# 12_CONSOLE.net
KiCad netlist of a schematic drawn in Altium Designer
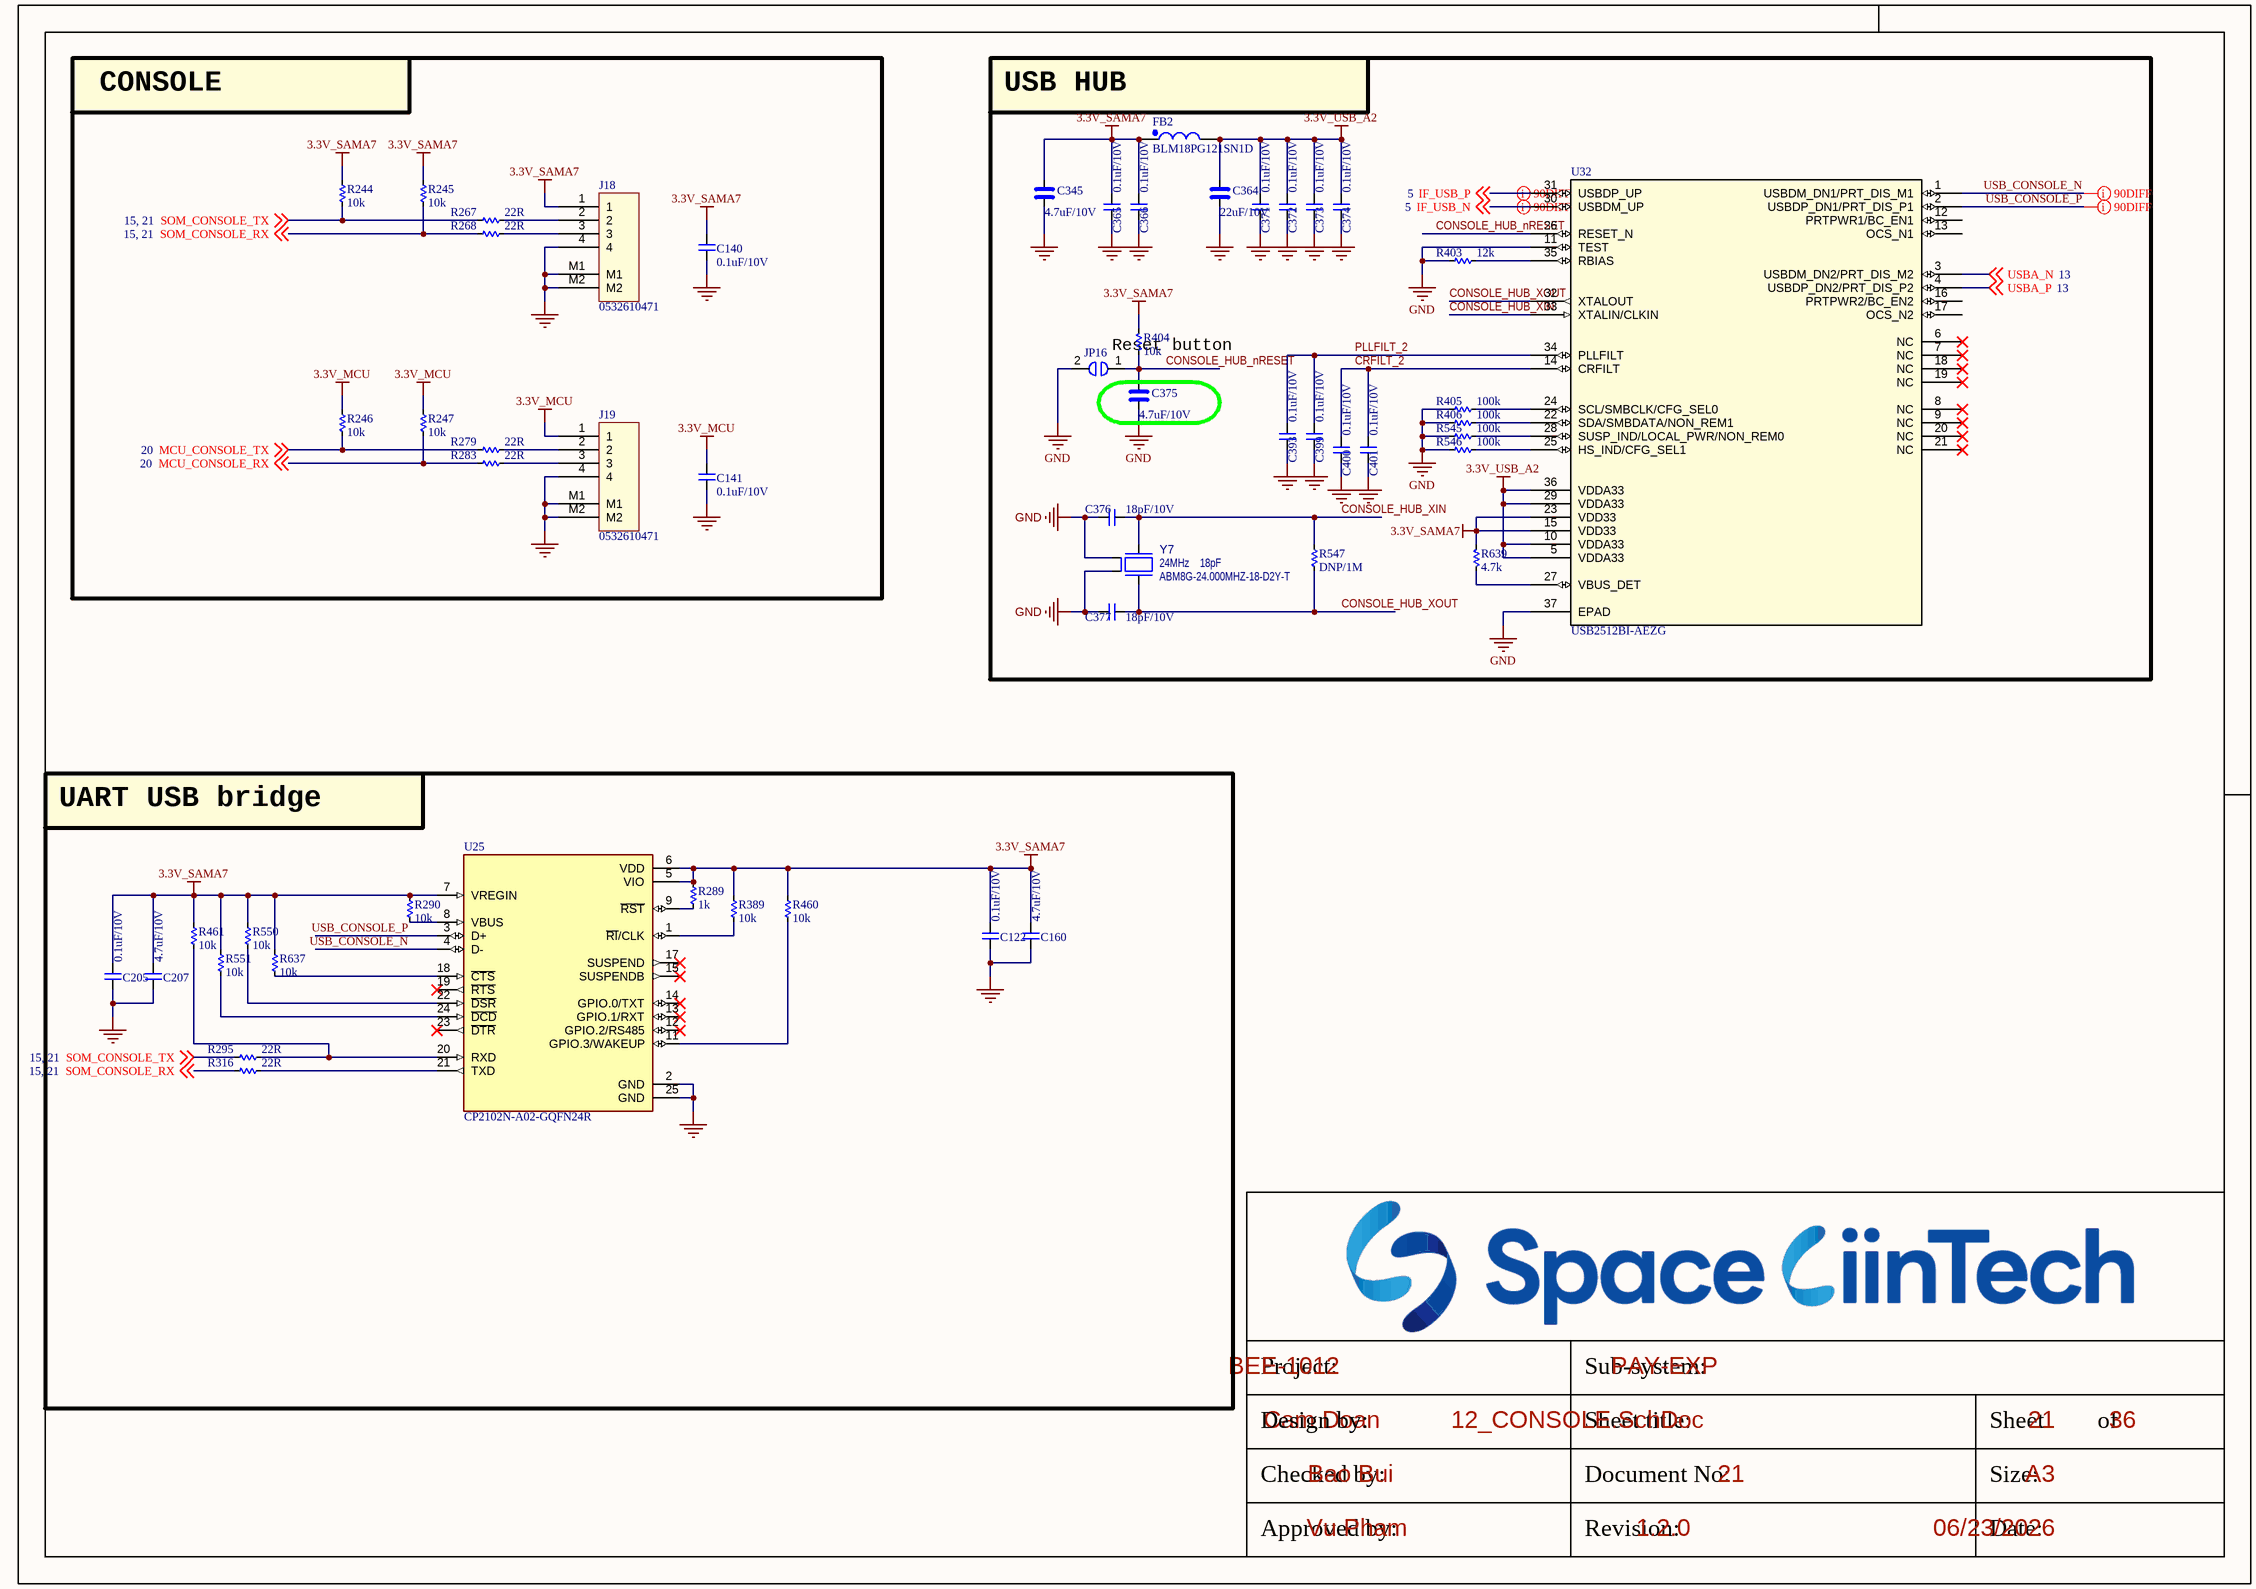
[diagram p0: 12_CONSOLE.SchDoc]

(export (version "E")
  (design (tool "Eeschema 10.0.6"))
  (components
    (comp (ref "C122")
      (value "0.1uF/10V")
      (footprint "CAP_C_1005X60")
      (description "CAP")
      (libsource (lib "LABLIB") (part "_CAP_C_2"))
    )
    (comp (ref "C140")
      (value "0.1uF/10V")
      (footprint "CAP_C_1005X60")
      (description "CAP")
      (libsource (lib "LABLIB") (part "_CAP_C_2"))
    )
    (comp (ref "C141")
      (value "0.1uF/10V")
      (footprint "CAP_C_1005X60")
      (description "CAP")
      (libsource (lib "LABLIB") (part "_CAP_C_2"))
    )
    (comp (ref "C160")
      (value "4.7uF/10V")
      (footprint "CAP_C_1005X60")
      (description "CAP")
      (libsource (lib "LABLIB") (part "_CAP_C_2"))
    )
    (comp (ref "C205")
      (value "0.1uF/10V")
      (footprint "CAP_C_1005X60")
      (description "CAP")
      (libsource (lib "LABLIB") (part "_CAP_C_2"))
    )
    (comp (ref "C207")
      (value "4.7uF/10V")
      (footprint "CAP_C_1005X60")
      (description "CAP")
      (libsource (lib "LABLIB") (part "_CAP_C_2"))
    )
    (comp (ref "C345")
      (value "4.7uF/10V")
      (footprint "CAP_C_1608X80")
      (description "CAP CHIP High Value")
      (libsource (lib "LABLIB") (part "_CAP_C_High_2"))
    )
    (comp (ref "C364")
      (value "22uF/10V")
      (footprint "CAP_C_1608X80")
      (description "CAP CHIP High Value")
      (libsource (lib "LABLIB") (part "_CAP_C_High_2"))
    )
    (comp (ref "C365")
      (value "0.1uF/10V")
      (footprint "CAP_C_1005X60")
      (description "CAP CHIP")
      (libsource (lib "LABLIB") (part "_CAP_C_2"))
    )
    (comp (ref "C366")
      (value "0.1uF/10V")
      (footprint "CAP_C_1005X60")
      (description "CAP CHIP")
      (libsource (lib "LABLIB") (part "_CAP_C_2"))
    )
    (comp (ref "C371")
      (value "0.1uF/10V")
      (footprint "CAP_C_1005X60")
      (description "CAP CHIP")
      (libsource (lib "LABLIB") (part "_CAP_C_2"))
    )
    (comp (ref "C372")
      (value "0.1uF/10V")
      (footprint "CAP_C_1005X60")
      (description "CAP CHIP")
      (libsource (lib "LABLIB") (part "_CAP_C_2"))
    )
    (comp (ref "C373")
      (value "0.1uF/10V")
      (footprint "CAP_C_1005X60")
      (description "CAP CHIP")
      (libsource (lib "LABLIB") (part "_CAP_C_2"))
    )
    (comp (ref "C374")
      (value "0.1uF/10V")
      (footprint "CAP_C_1005X60")
      (description "CAP CHIP")
      (libsource (lib "LABLIB") (part "_CAP_C_2"))
    )
    (comp (ref "C375")
      (value "4.7uF/10V")
      (footprint "CAP_C_1608X80")
      (description "CAP CHIP High Value")
      (libsource (lib "LABLIB") (part "_CAP_C_High_2"))
    )
    (comp (ref "C376")
      (value "18pF/10V")
      (footprint "CAP_C_1005X60")
      (description "CAP CHIP")
      (libsource (lib "LABLIB") (part "_CAP_C_2"))
    )
    (comp (ref "C377")
      (value "18pF/10V")
      (footprint "CAP_C_1005X60")
      (description "CAP CHIP")
      (libsource (lib "LABLIB") (part "_CAP_C_2"))
    )
    (comp (ref "C393")
      (value "0.1uF/10V")
      (footprint "CAP_C_1005X60")
      (description "CAP CHIP")
      (libsource (lib "LABLIB") (part "_CAP_C_2"))
    )
    (comp (ref "C399")
      (value "0.1uF/10V")
      (footprint "CAP_C_1005X60")
      (description "CAP CHIP")
      (libsource (lib "LABLIB") (part "_CAP_C_2"))
    )
    (comp (ref "C400")
      (value "0.1uF/10V")
      (footprint "CAP_C_1005X60")
      (description "CAP CHIP")
      (libsource (lib "LABLIB") (part "_CAP_C_2"))
    )
    (comp (ref "C401")
      (value "0.1uF/10V")
      (footprint "CAP_C_1005X60")
      (description "CAP CHIP")
      (libsource (lib "LABLIB") (part "_CAP_C_2"))
    )
    (comp (ref "FB2")
      (value "BLM18PG121SN1D")
      (footprint "IND_C_1608X60")
      (libsource (lib "LABLIB") (part "_IND"))
    )
    (comp (ref "J18")
      (value "0532610471")
      (footprint "MOLEX_0532610471")
      (libsource (lib "LABLIB") (part "Header 4x1_2M"))
    )
    (comp (ref "J19")
      (value "0532610471")
      (footprint "MOLEX_0532610471")
      (libsource (lib "LABLIB") (part "Header 4x1_2M"))
    )
    (comp (ref "JP16")
      (value "~")
      (footprint "TESTPOINT_SHORT_120X100_60")
      (libsource (lib "LABLIB") (part "JUMPER_1_1"))
    )
    (comp (ref "R244")
      (value "10k")
      (footprint "RES_C_1005X40")
      (description "RES")
      (libsource (lib "LABLIB") (part "_RES_B_2"))
    )
    (comp (ref "R245")
      (value "10k")
      (footprint "RES_C_1005X40")
      (description "RES")
      (libsource (lib "LABLIB") (part "_RES_B_2"))
    )
    (comp (ref "R246")
      (value "10k")
      (footprint "RES_C_1005X40")
      (description "RES")
      (libsource (lib "LABLIB") (part "_RES_B_2"))
    )
    (comp (ref "R247")
      (value "10k")
      (footprint "RES_C_1005X40")
      (description "RES")
      (libsource (lib "LABLIB") (part "_RES_B_2"))
    )
    (comp (ref "R267")
      (value "22R")
      (footprint "RES_C_1005X40")
      (description "RES")
      (libsource (lib "LABLIB") (part "_RES_B_2"))
    )
    (comp (ref "R268")
      (value "22R")
      (footprint "RES_C_1005X40")
      (description "RES")
      (libsource (lib "LABLIB") (part "_RES_B_2"))
    )
    (comp (ref "R279")
      (value "22R")
      (footprint "RES_C_1005X40")
      (description "RES")
      (libsource (lib "LABLIB") (part "_RES_B_2"))
    )
    (comp (ref "R283")
      (value "22R")
      (footprint "RES_C_1005X40")
      (description "RES")
      (libsource (lib "LABLIB") (part "_RES_B_2"))
    )
    (comp (ref "R289")
      (value "1k")
      (footprint "RES_C_1005X40")
      (description "RES")
      (libsource (lib "LABLIB") (part "_RES_B_2"))
    )
    (comp (ref "R290")
      (value "10k")
      (footprint "RES_C_1005X40")
      (description "RES")
      (libsource (lib "LABLIB") (part "_RES_B_2"))
    )
    (comp (ref "R295")
      (value "22R")
      (footprint "RES_C_1005X40")
      (description "RES")
      (libsource (lib "LABLIB") (part "_RES_B_2"))
    )
    (comp (ref "R316")
      (value "22R")
      (footprint "RES_C_1005X40")
      (description "RES")
      (libsource (lib "LABLIB") (part "_RES_B_2"))
    )
    (comp (ref "R389")
      (value "10k")
      (footprint "RES_C_1005X40")
      (description "RES")
      (libsource (lib "LABLIB") (part "_RES_B_2"))
    )
    (comp (ref "R403")
      (value "12k")
      (footprint "RES_C_1005X40")
      (description "RES")
      (libsource (lib "LABLIB") (part "_RES_B_2"))
    )
    (comp (ref "R404")
      (value "10k")
      (footprint "RES_C_1005X40")
      (description "RES")
      (libsource (lib "LABLIB") (part "_RES_B_2"))
    )
    (comp (ref "R405")
      (value "100k")
      (footprint "RES_C_1005X40")
      (description "RES")
      (libsource (lib "LABLIB") (part "_RES_B_2"))
    )
    (comp (ref "R406")
      (value "100k")
      (footprint "RES_C_1005X40")
      (description "RES")
      (libsource (lib "LABLIB") (part "_RES_B_2"))
    )
    (comp (ref "R460")
      (value "10k")
      (footprint "RES_C_1005X40")
      (description "RES")
      (libsource (lib "LABLIB") (part "_RES_B_2"))
    )
    (comp (ref "R461")
      (value "10k")
      (footprint "RES_C_1005X40")
      (description "RES")
      (libsource (lib "LABLIB") (part "_RES_B_2"))
    )
    (comp (ref "R545")
      (value "100k")
      (footprint "RES_C_1005X40")
      (description "RES")
      (libsource (lib "LABLIB") (part "_RES_B_2"))
    )
    (comp (ref "R546")
      (value "100k")
      (footprint "RES_C_1005X40")
      (description "RES")
      (libsource (lib "LABLIB") (part "_RES_B_2"))
    )
    (comp (ref "R547")
      (value "DNP/1M")
      (footprint "RES_C_1005X40")
      (description "RES")
      (libsource (lib "LABLIB") (part "_RES_B_2"))
    )
    (comp (ref "R550")
      (value "10k")
      (footprint "RES_C_1005X40")
      (description "RES")
      (libsource (lib "LABLIB") (part "_RES_B_2"))
    )
    (comp (ref "R551")
      (value "10k")
      (footprint "RES_C_1005X40")
      (description "RES")
      (libsource (lib "LABLIB") (part "_RES_B_2"))
    )
    (comp (ref "R637")
      (value "10k")
      (footprint "RES_C_1005X40")
      (description "RES")
      (libsource (lib "LABLIB") (part "_RES_B_2"))
    )
    (comp (ref "R639")
      (value "4.7k")
      (footprint "RES_C_1005X40")
      (description "RES")
      (libsource (lib "LABLIB") (part "_RES_B_2"))
    )
    (comp (ref "U25")
      (value "CP2102N-A02-GQFN24R")
      (footprint "QFN50P400X400X80-25N")
      (libsource (lib "LABLIB") (part "IC_USB_toUART_CP2102N-A02-GQFN24R"))
    )
    (comp (ref "U32")
      (value "USB2512BI-AEZG")
      (footprint "QFN36_6X6MC_MCH")
      (description "Description")
      (fields (field (name "COPYRIGHT") "Copyright (C) 2026 Ultra Librarian. All rights reserved."))
      (libsource (lib "LABLIB") (part "IC_USB_HUB_USB2512BI-AEZG"))
    )
    (comp (ref "Y7")
      (value "24MHz")
      (footprint "CRYSTAL_ABM8G")
      (description "Crystal")
      (fields
        (field (name "LOAD CAPACITANCE") "18pF")
        (field (name "MANUFACTURER PART NUMBER 1") "ABM8G-24.000MHZ-18-D2Y-T")
        (field (name "Comment") "Crystal 4 Pins")
        (field (name "OWNER") "Mark Loper")
      )
      (libsource (lib "MCHP-CDB") (part "Crystal 4 Pins"))
    )
  )
  (nets
    (net (code "1") (name "/CONSOLE_HUB_XIN") (class "Default")
      (node (ref "C376") (pin "1") (pinfunction "1_1") (pintype "passive"))
      (node (ref "R547") (pin "1") (pinfunction "1_1") (pintype "passive"))
      (node (ref "U32") (pin "33") (pinfunction "XTALIN/CLKIN_33") (pintype "input"))
      (node (ref "Y7") (pin "3") (pinfunction "Osc2_3") (pintype "passive"))
    )
    (net (code "2") (name "/CONSOLE_HUB_XOUT") (class "Default")
      (node (ref "C377") (pin "1") (pinfunction "1_1") (pintype "passive"))
      (node (ref "R547") (pin "2") (pinfunction "2_2") (pintype "passive"))
      (node (ref "U32") (pin "32") (pinfunction "XTALOUT_32") (pintype "output"))
      (node (ref "Y7") (pin "1") (pinfunction "Osc1_1") (pintype "passive"))
    )
    (net (code "3") (name "/CONSOLE_HUB_nRESET") (class "Default")
      (node (ref "C375") (pin "1") (pinfunction "1_1") (pintype "passive"))
      (node (ref "JP16") (pin "1") (pinfunction "1_1") (pintype "passive"))
      (node (ref "R404") (pin "2") (pinfunction "2_2") (pintype "passive"))
      (node (ref "U32") (pin "26") (pinfunction "RESET_N_26") (pintype "bidirectional"))
    )
    (net (code "4") (name "/CRFILT_2") (class "Default")
      (node (ref "C400") (pin "2") (pinfunction "2_2") (pintype "passive"))
      (node (ref "C401") (pin "2") (pinfunction "2_2") (pintype "passive"))
      (node (ref "U32") (pin "14") (pinfunction "CRFILT_14") (pintype "bidirectional"))
    )
    (net (code "5") (name "/PLLFILT_2") (class "Default")
      (node (ref "C393") (pin "2") (pinfunction "2_2") (pintype "passive"))
      (node (ref "C399") (pin "2") (pinfunction "2_2") (pintype "passive"))
      (node (ref "U32") (pin "34") (pinfunction "PLLFILT_34") (pintype "bidirectional"))
    )
    (net (code "6") (name "/USB_CONSOLE_N") (class "Default")
      (node (ref "U25") (pin "4") (pinfunction "D-_4") (pintype "bidirectional"))
      (node (ref "U32") (pin "1") (pinfunction "USBDM_DN1/PRT_DIS_M1_1") (pintype "bidirectional"))
    )
    (net (code "7") (name "/USB_CONSOLE_P") (class "Default")
      (node (ref "U25") (pin "3") (pinfunction "D+_3") (pintype "bidirectional"))
      (node (ref "U32") (pin "2") (pinfunction "USBDP_DN1/PRT_DIS_P1_2") (pintype "bidirectional"))
    )
    (net (code "8") (name "3.3V_MCU") (class "Default")
      (node (ref "C141") (pin "2") (pinfunction "2_2") (pintype "passive"))
      (node (ref "J19") (pin "1") (pinfunction "1_1") (pintype "passive"))
      (node (ref "R246") (pin "2") (pinfunction "2_2") (pintype "passive"))
      (node (ref "R247") (pin "2") (pinfunction "2_2") (pintype "passive"))
    )
    (net (code "9") (name "3.3V_SAMA7") (class "Default")
      (node (ref "C122") (pin "1") (pinfunction "1_1") (pintype "passive"))
      (node (ref "C140") (pin "2") (pinfunction "2_2") (pintype "passive"))
      (node (ref "C160") (pin "1") (pinfunction "1_1") (pintype "passive"))
      (node (ref "C205") (pin "1") (pinfunction "1_1") (pintype "passive"))
      (node (ref "C207") (pin "1") (pinfunction "1_1") (pintype "passive"))
      (node (ref "C345") (pin "1") (pinfunction "1_1") (pintype "passive"))
      (node (ref "C365") (pin "2") (pinfunction "2_2") (pintype "passive"))
      (node (ref "C366") (pin "2") (pinfunction "2_2") (pintype "passive"))
      (node (ref "FB2") (pin "1") (pinfunction "1_1") (pintype "passive"))
      (node (ref "J18") (pin "1") (pinfunction "1_1") (pintype "passive"))
      (node (ref "R244") (pin "2") (pinfunction "2_2") (pintype "passive"))
      (node (ref "R245") (pin "2") (pinfunction "2_2") (pintype "passive"))
      (node (ref "R289") (pin "2") (pinfunction "2_2") (pintype "passive"))
      (node (ref "R290") (pin "2") (pinfunction "2_2") (pintype "passive"))
      (node (ref "R389") (pin "2") (pinfunction "2_2") (pintype "passive"))
      (node (ref "R404") (pin "1") (pinfunction "1_1") (pintype "passive"))
      (node (ref "R460") (pin "2") (pinfunction "2_2") (pintype "passive"))
      (node (ref "R461") (pin "2") (pinfunction "2_2") (pintype "passive"))
      (node (ref "R550") (pin "2") (pinfunction "2_2") (pintype "passive"))
      (node (ref "R551") (pin "2") (pinfunction "2_2") (pintype "passive"))
      (node (ref "R637") (pin "2") (pinfunction "2_2") (pintype "passive"))
      (node (ref "R639") (pin "1") (pinfunction "1_1") (pintype "passive"))
      (node (ref "U25") (pin "5") (pinfunction "VIO_5") (pintype "power_in"))
      (node (ref "U25") (pin "6") (pinfunction "VDD_6") (pintype "power_in"))
      (node (ref "U25") (pin "7") (pinfunction "VREGIN_7") (pintype "input"))
      (node (ref "U32") (pin "15") (pinfunction "VDD33_15") (pintype "power_in"))
      (node (ref "U32") (pin "23") (pinfunction "VDD33_23") (pintype "power_in"))
    )
    (net (code "10") (name "3.3V_USB_A2") (class "Default")
      (node (ref "C364") (pin "1") (pinfunction "1_1") (pintype "passive"))
      (node (ref "C371") (pin "2") (pinfunction "2_2") (pintype "passive"))
      (node (ref "C372") (pin "2") (pinfunction "2_2") (pintype "passive"))
      (node (ref "C373") (pin "2") (pinfunction "2_2") (pintype "passive"))
      (node (ref "C374") (pin "2") (pinfunction "2_2") (pintype "passive"))
      (node (ref "FB2") (pin "2") (pinfunction "2_2") (pintype "passive"))
      (node (ref "U32") (pin "10") (pinfunction "VDDA33_10") (pintype "power_in"))
      (node (ref "U32") (pin "29") (pinfunction "VDDA33_29") (pintype "power_in"))
      (node (ref "U32") (pin "36") (pinfunction "VDDA33_36") (pintype "power_in"))
      (node (ref "U32") (pin "5") (pinfunction "VDDA33_5") (pintype "power_in"))
    )
    (net (code "11") (name "GND") (class "Default")
      (node (ref "C122") (pin "2") (pinfunction "2_2") (pintype "passive"))
      (node (ref "C140") (pin "1") (pinfunction "1_1") (pintype "passive"))
      (node (ref "C141") (pin "1") (pinfunction "1_1") (pintype "passive"))
      (node (ref "C160") (pin "2") (pinfunction "2_2") (pintype "passive"))
      (node (ref "C205") (pin "2") (pinfunction "2_2") (pintype "passive"))
      (node (ref "C207") (pin "2") (pinfunction "2_2") (pintype "passive"))
      (node (ref "C345") (pin "2") (pinfunction "2_2") (pintype "passive"))
      (node (ref "C364") (pin "2") (pinfunction "2_2") (pintype "passive"))
      (node (ref "C365") (pin "1") (pinfunction "1_1") (pintype "passive"))
      (node (ref "C366") (pin "1") (pinfunction "1_1") (pintype "passive"))
      (node (ref "C371") (pin "1") (pinfunction "1_1") (pintype "passive"))
      (node (ref "C372") (pin "1") (pinfunction "1_1") (pintype "passive"))
      (node (ref "C373") (pin "1") (pinfunction "1_1") (pintype "passive"))
      (node (ref "C374") (pin "1") (pinfunction "1_1") (pintype "passive"))
      (node (ref "C375") (pin "2") (pinfunction "2_2") (pintype "passive"))
      (node (ref "C376") (pin "2") (pinfunction "2_2") (pintype "passive"))
      (node (ref "C377") (pin "2") (pinfunction "2_2") (pintype "passive"))
      (node (ref "C393") (pin "1") (pinfunction "1_1") (pintype "passive"))
      (node (ref "C399") (pin "1") (pinfunction "1_1") (pintype "passive"))
      (node (ref "C400") (pin "1") (pinfunction "1_1") (pintype "passive"))
      (node (ref "C401") (pin "1") (pinfunction "1_1") (pintype "passive"))
      (node (ref "J18") (pin "4") (pinfunction "4_4") (pintype "passive"))
      (node (ref "J18") (pin "M1") (pinfunction "M1_M1") (pintype "passive"))
      (node (ref "J18") (pin "M2") (pinfunction "M2_M2") (pintype "passive"))
      (node (ref "J19") (pin "4") (pinfunction "4_4") (pintype "passive"))
      (node (ref "J19") (pin "M1") (pinfunction "M1_M1") (pintype "passive"))
      (node (ref "J19") (pin "M2") (pinfunction "M2_M2") (pintype "passive"))
      (node (ref "JP16") (pin "2") (pinfunction "2_2") (pintype "passive"))
      (node (ref "R403") (pin "1") (pinfunction "1_1") (pintype "passive"))
      (node (ref "R405") (pin "1") (pinfunction "1_1") (pintype "passive"))
      (node (ref "R406") (pin "1") (pinfunction "1_1") (pintype "passive"))
      (node (ref "R545") (pin "1") (pinfunction "1_1") (pintype "passive"))
      (node (ref "R546") (pin "1") (pinfunction "1_1") (pintype "passive"))
      (node (ref "U25") (pin "2") (pinfunction "GND_2") (pintype "power_in"))
      (node (ref "U25") (pin "25") (pinfunction "GND_25") (pintype "power_in"))
      (node (ref "U32") (pin "11") (pinfunction "TEST_11") (pintype "bidirectional"))
      (node (ref "U32") (pin "37") (pinfunction "EPAD_37") (pintype "passive"))
      (node (ref "Y7") (pin "2") (pinfunction "GND_2") (pintype "power_in"))
      (node (ref "Y7") (pin "4") (pinfunction "GND_4") (pintype "power_in"))
    )
    (net (code "12") (name "IF_USB_N") (class "Default")
      (node (ref "U32") (pin "30") (pinfunction "USBDM_UP_30") (pintype "bidirectional"))
    )
    (net (code "13") (name "IF_USB_P") (class "Default")
      (node (ref "U32") (pin "31") (pinfunction "USBDP_UP_31") (pintype "bidirectional"))
    )
    (net (code "14") (name "MCU_CONSOLE_RX") (class "Default")
      (node (ref "R247") (pin "1") (pinfunction "1_1") (pintype "passive"))
      (node (ref "R283") (pin "2") (pinfunction "2_2") (pintype "passive"))
    )
    (net (code "15") (name "MCU_CONSOLE_TX") (class "Default")
      (node (ref "R246") (pin "1") (pinfunction "1_1") (pintype "passive"))
      (node (ref "R279") (pin "2") (pinfunction "2_2") (pintype "passive"))
    )
    (net (code "16") (name "Net-(J18-Pad2)") (class "Default")
      (node (ref "J18") (pin "2") (pinfunction "2_2") (pintype "passive"))
      (node (ref "R267") (pin "1") (pinfunction "1_1") (pintype "passive"))
    )
    (net (code "17") (name "Net-(J18-Pad3)") (class "Default")
      (node (ref "J18") (pin "3") (pinfunction "3_3") (pintype "passive"))
      (node (ref "R268") (pin "1") (pinfunction "1_1") (pintype "passive"))
    )
    (net (code "18") (name "Net-(J19-Pad2)") (class "Default")
      (node (ref "J19") (pin "2") (pinfunction "2_2") (pintype "passive"))
      (node (ref "R279") (pin "1") (pinfunction "1_1") (pintype "passive"))
    )
    (net (code "19") (name "Net-(J19-Pad3)") (class "Default")
      (node (ref "J19") (pin "3") (pinfunction "3_3") (pintype "passive"))
      (node (ref "R283") (pin "1") (pinfunction "1_1") (pintype "passive"))
    )
    (net (code "20") (name "Net-(U25-GPIO.3{slash}WAKEUP)") (class "Default")
      (node (ref "R460") (pin "1") (pinfunction "1_1") (pintype "passive"))
      (node (ref "U25") (pin "11") (pinfunction "GPIO.3/WAKEUP_11") (pintype "bidirectional"))
    )
    (net (code "21") (name "Net-(U25-RXD)") (class "Default")
      (node (ref "R295") (pin "1") (pinfunction "1_1") (pintype "passive"))
      (node (ref "R461") (pin "1") (pinfunction "1_1") (pintype "passive"))
      (node (ref "U25") (pin "20") (pinfunction "RXD_20") (pintype "input"))
    )
    (net (code "22") (name "Net-(U25-TXD)") (class "Default")
      (node (ref "R316") (pin "1") (pinfunction "1_1") (pintype "passive"))
      (node (ref "U25") (pin "21") (pinfunction "TXD_21") (pintype "output"))
    )
    (net (code "23") (name "Net-(U25-VBUS)") (class "Default")
      (node (ref "R290") (pin "1") (pinfunction "1_1") (pintype "passive"))
      (node (ref "U25") (pin "8") (pinfunction "VBUS_8") (pintype "input"))
    )
    (net (code "24") (name "Net-(U25-~{CTS})") (class "Default")
      (node (ref "R637") (pin "1") (pinfunction "1_1") (pintype "passive"))
      (node (ref "U25") (pin "18") (pinfunction "~{CTS}_18") (pintype "input"))
    )
    (net (code "25") (name "Net-(U25-~{DCD})") (class "Default")
      (node (ref "R551") (pin "1") (pinfunction "1_1") (pintype "passive"))
      (node (ref "U25") (pin "24") (pinfunction "~{DCD}_24") (pintype "input"))
    )
    (net (code "26") (name "Net-(U25-~{DSR})") (class "Default")
      (node (ref "R550") (pin "1") (pinfunction "1_1") (pintype "passive"))
      (node (ref "U25") (pin "22") (pinfunction "~{DSR}_22") (pintype "input"))
    )
    (net (code "27") (name "Net-(U25-~{RI}{slash}CLK)") (class "Default")
      (node (ref "R389") (pin "1") (pinfunction "1_1") (pintype "passive"))
      (node (ref "U25") (pin "1") (pinfunction "~{RI}/CLK_1") (pintype "bidirectional"))
    )
    (net (code "28") (name "Net-(U25-~{RST})") (class "Default")
      (node (ref "R289") (pin "1") (pinfunction "1_1") (pintype "passive"))
      (node (ref "U25") (pin "9") (pinfunction "~{RST}_9") (pintype "bidirectional"))
    )
    (net (code "29") (name "Net-(U32-HS_IND{slash}CFG_SEL1)") (class "Default")
      (node (ref "R546") (pin "2") (pinfunction "2_2") (pintype "passive"))
      (node (ref "U32") (pin "25") (pinfunction "HS_IND/CFG_SEL1_25") (pintype "bidirectional"))
    )
    (net (code "30") (name "Net-(U32-RBIAS)") (class "Default")
      (node (ref "R403") (pin "2") (pinfunction "2_2") (pintype "passive"))
      (node (ref "U32") (pin "35") (pinfunction "RBIAS_35") (pintype "bidirectional"))
    )
    (net (code "31") (name "Net-(U32-SCL{slash}SMBCLK{slash}CFG_SEL0)") (class "Default")
      (node (ref "R405") (pin "2") (pinfunction "2_2") (pintype "passive"))
      (node (ref "U32") (pin "24") (pinfunction "SCL/SMBCLK/CFG_SEL0_24") (pintype "bidirectional"))
    )
    (net (code "32") (name "Net-(U32-SDA{slash}SMBDATA{slash}NON_REM1)") (class "Default")
      (node (ref "R406") (pin "2") (pinfunction "2_2") (pintype "passive"))
      (node (ref "U32") (pin "22") (pinfunction "SDA/SMBDATA/NON_REM1_22") (pintype "bidirectional"))
    )
    (net (code "33") (name "Net-(U32-SUSP_IND{slash}LOCAL_PWR{slash}NON_REM0)") (class "Default")
      (node (ref "R545") (pin "2") (pinfunction "2_2") (pintype "passive"))
      (node (ref "U32") (pin "28") (pinfunction "SUSP_IND/LOCAL_PWR/NON_REM0_28") (pintype "bidirectional"))
    )
    (net (code "34") (name "Net-(U32-VBUS_DET)") (class "Default")
      (node (ref "R639") (pin "2") (pinfunction "2_2") (pintype "passive"))
      (node (ref "U32") (pin "27") (pinfunction "VBUS_DET_27") (pintype "bidirectional"))
    )
    (net (code "35") (name "SOM_CONSOLE_RX") (class "Default")
      (node (ref "R245") (pin "1") (pinfunction "1_1") (pintype "passive"))
      (node (ref "R268") (pin "2") (pinfunction "2_2") (pintype "passive"))
      (node (ref "R316") (pin "2") (pinfunction "2_2") (pintype "passive"))
    )
    (net (code "36") (name "SOM_CONSOLE_TX") (class "Default")
      (node (ref "R244") (pin "1") (pinfunction "1_1") (pintype "passive"))
      (node (ref "R267") (pin "2") (pinfunction "2_2") (pintype "passive"))
      (node (ref "R295") (pin "2") (pinfunction "2_2") (pintype "passive"))
    )
    (net (code "37") (name "USBA_N") (class "Default")
      (node (ref "U32") (pin "3") (pinfunction "USBDM_DN2/PRT_DIS_M2_3") (pintype "bidirectional"))
    )
    (net (code "38") (name "USBA_P") (class "Default")
      (node (ref "U32") (pin "4") (pinfunction "USBDP_DN2/PRT_DIS_P2_4") (pintype "bidirectional"))
    )
    (net (code "39") (name "unconnected-(U25-GPIO.0{slash}TXT-Pad14)") (class "Default")
      (node (ref "U25") (pin "14") (pinfunction "GPIO.0/TXT_14") (pintype "bidirectional+no_connect"))
    )
    (net (code "40") (name "unconnected-(U25-GPIO.1{slash}RXT-Pad13)") (class "Default")
      (node (ref "U25") (pin "13") (pinfunction "GPIO.1/RXT_13") (pintype "bidirectional+no_connect"))
    )
    (net (code "41") (name "unconnected-(U25-GPIO.2{slash}RS485-Pad12)") (class "Default")
      (node (ref "U25") (pin "12") (pinfunction "GPIO.2/RS485_12") (pintype "bidirectional+no_connect"))
    )
    (net (code "42") (name "unconnected-(U25-SUSPEND-Pad17)") (class "Default")
      (node (ref "U25") (pin "17") (pinfunction "SUSPEND_17") (pintype "output+no_connect"))
    )
    (net (code "43") (name "unconnected-(U25-SUSPENDB-Pad15)") (class "Default")
      (node (ref "U25") (pin "15") (pinfunction "SUSPENDB_15") (pintype "output+no_connect"))
    )
    (net (code "44") (name "unconnected-(U25-~{DTR}-Pad23)") (class "Default")
      (node (ref "U25") (pin "23") (pinfunction "~{DTR}_23") (pintype "output+no_connect"))
    )
    (net (code "45") (name "unconnected-(U25-~{RTS}-Pad19)") (class "Default")
      (node (ref "U25") (pin "19") (pinfunction "~{RTS}_19") (pintype "output+no_connect"))
    )
    (net (code "46") (name "unconnected-(U32-NC-Pad6)") (class "Default")
      (node (ref "U32") (pin "6") (pinfunction "NC_6") (pintype "passive+no_connect"))
    )
    (net (code "47") (name "unconnected-(U32-NC-Pad7)") (class "Default")
      (node (ref "U32") (pin "7") (pinfunction "NC_7") (pintype "passive+no_connect"))
    )
    (net (code "48") (name "unconnected-(U32-NC-Pad8)") (class "Default")
      (node (ref "U32") (pin "8") (pinfunction "NC_8") (pintype "passive+no_connect"))
    )
    (net (code "49") (name "unconnected-(U32-NC-Pad9)") (class "Default")
      (node (ref "U32") (pin "9") (pinfunction "NC_9") (pintype "passive+no_connect"))
    )
    (net (code "50") (name "unconnected-(U32-NC-Pad18)") (class "Default")
      (node (ref "U32") (pin "18") (pinfunction "NC_18") (pintype "passive+no_connect"))
    )
    (net (code "51") (name "unconnected-(U32-NC-Pad19)") (class "Default")
      (node (ref "U32") (pin "19") (pinfunction "NC_19") (pintype "passive+no_connect"))
    )
    (net (code "52") (name "unconnected-(U32-NC-Pad20)") (class "Default")
      (node (ref "U32") (pin "20") (pinfunction "NC_20") (pintype "passive+no_connect"))
    )
    (net (code "53") (name "unconnected-(U32-NC-Pad21)") (class "Default")
      (node (ref "U32") (pin "21") (pinfunction "NC_21") (pintype "passive+no_connect"))
    )
    (net (code "54") (name "unconnected-(U32-OCS_N1-Pad13)") (class "Default")
      (node (ref "U32") (pin "13") (pinfunction "OCS_N1_13") (pintype "bidirectional"))
    )
    (net (code "55") (name "unconnected-(U32-OCS_N2-Pad17)") (class "Default")
      (node (ref "U32") (pin "17") (pinfunction "OCS_N2_17") (pintype "bidirectional"))
    )
    (net (code "56") (name "unconnected-(U32-PRTPWR1{slash}BC_EN1-Pad12)") (class "Default")
      (node (ref "U32") (pin "12") (pinfunction "PRTPWR1/BC_EN1_12") (pintype "bidirectional"))
    )
    (net (code "57") (name "unconnected-(U32-PRTPWR2{slash}BC_EN2-Pad16)") (class "Default")
      (node (ref "U32") (pin "16") (pinfunction "PRTPWR2/BC_EN2_16") (pintype "bidirectional"))
    )
  )
)
